# Bio_v4_LCD.net
KiCad netlist of a schematic drawn in EAGLE
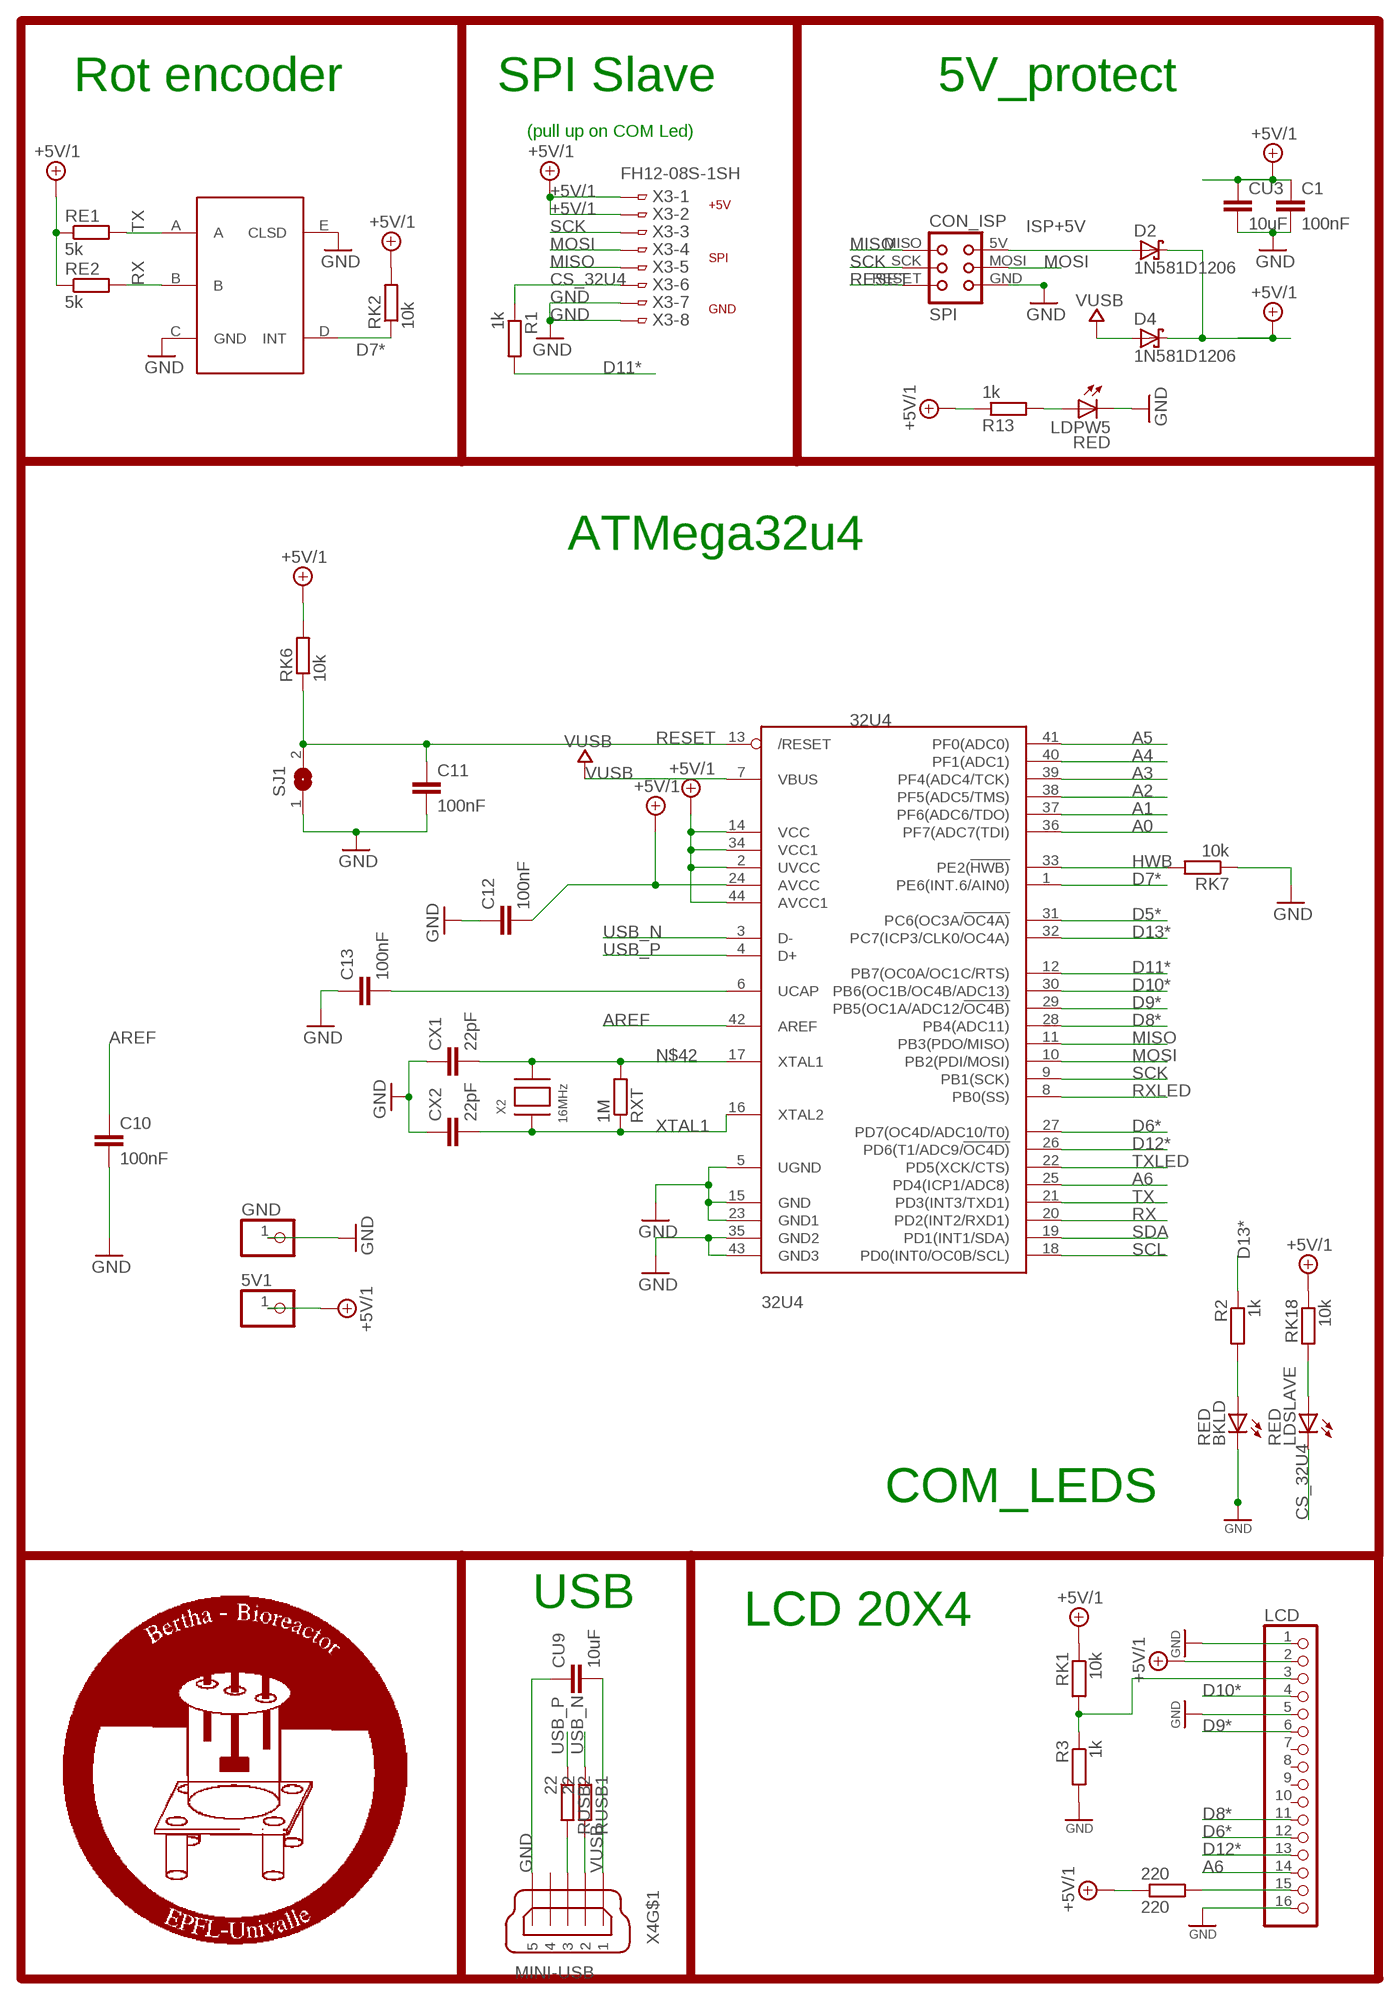
[diagram p0: schematic, sheet 1]

(export (version "E")
  (design (tool "Eeschema 10.0.6"))
  (components
    (comp (ref "5V1")
      (value "PINHD-1X1")
      (footprint "eagle-import:1X01")
      (libsource (lib "eagle-import") (part "PINHD-1X1"))
    )
    (comp (ref "32U4")
      (value "32U4")
      (footprint "eagle-import:TQFP44")
      (libsource (lib "eagle-import") (part "ATMEGA32U4-AU"))
    )
    (comp (ref "220")
      (value "220")
      (footprint "eagle-import:R0805")
      (libsource (lib "eagle-import") (part "R-EU_R0805"))
    )
    (comp (ref "BKLD")
      (value "RED")
      (footprint "eagle-import:CHIP-LED0805")
      (libsource (lib "eagle-import") (part "LEDCHIP-LED0805"))
    )
    (comp (ref "C1")
      (value "100nF")
      (footprint "eagle-import:C1206")
      (libsource (lib "eagle-import") (part "C-EUC1206"))
    )
    (comp (ref "C10")
      (value "100nF")
      (footprint "eagle-import:C1206")
      (libsource (lib "eagle-import") (part "C-EUC1206"))
    )
    (comp (ref "C11")
      (value "100nF")
      (footprint "eagle-import:C1206")
      (libsource (lib "eagle-import") (part "C-EUC1206"))
    )
    (comp (ref "C12")
      (value "100nF")
      (footprint "eagle-import:C1206")
      (libsource (lib "eagle-import") (part "C-EUC1206"))
    )
    (comp (ref "C13")
      (value "100nF")
      (footprint "eagle-import:C1206")
      (libsource (lib "eagle-import") (part "C-EUC1206"))
    )
    (comp (ref "CON_ISP")
      (value "SPI")
      (footprint "eagle-import:TC2030-MCP-NL")
      (libsource (lib "eagle-import") (part "TINYISPT"))
    )
    (comp (ref "CU3")
      (value "10uF")
      (footprint "eagle-import:C1206")
      (libsource (lib "eagle-import") (part "C-EUC1206"))
    )
    (comp (ref "CU9")
      (value "10uF")
      (footprint "eagle-import:C1206")
      (libsource (lib "eagle-import") (part "C-EUC1206"))
    )
    (comp (ref "CX1")
      (value "22pF")
      (footprint "eagle-import:C1206")
      (libsource (lib "eagle-import") (part "C-EUC1206"))
    )
    (comp (ref "CX2")
      (value "22pF")
      (footprint "eagle-import:C1206")
      (libsource (lib "eagle-import") (part "C-EUC1206"))
    )
    (comp (ref "D2")
      (value "1N581D1206")
      (footprint "eagle-import:LED-1206")
      (libsource (lib "eagle-import") (part "1N581D1206"))
    )
    (comp (ref "D4")
      (value "1N581D1206")
      (footprint "eagle-import:LED-1206")
      (libsource (lib "eagle-import") (part "1N581D1206"))
    )
    (comp (ref "GND")
      (value "PINHD-1X1")
      (footprint "eagle-import:1X01")
      (libsource (lib "eagle-import") (part "PINHD-1X1"))
    )
    (comp (ref "LCD")
      (value "LCD-HEADER")
      (footprint "eagle-import:1X16")
      (libsource (lib "eagle-import") (part "LCD-HEADER"))
    )
    (comp (ref "LDPW5")
      (value "RED")
      (footprint "eagle-import:CHIP-LED0805")
      (libsource (lib "eagle-import") (part "LEDCHIP-LED0805"))
    )
    (comp (ref "LDSLAVE")
      (value "RED")
      (footprint "eagle-import:CHIP-LED0805")
      (libsource (lib "eagle-import") (part "LEDCHIP-LED0805"))
    )
    (comp (ref "R1")
      (value "1k")
      (footprint "eagle-import:R0805")
      (libsource (lib "eagle-import") (part "R-EU_R0805"))
    )
    (comp (ref "R2")
      (value "1k")
      (footprint "eagle-import:R0805")
      (libsource (lib "eagle-import") (part "R-EU_R0805"))
    )
    (comp (ref "R3")
      (value "1k")
      (footprint "eagle-import:R0805")
      (libsource (lib "eagle-import") (part "R-EU_R0805"))
    )
    (comp (ref "R13")
      (value "1k")
      (footprint "eagle-import:R0805")
      (libsource (lib "eagle-import") (part "resistor_R-EU_R0805"))
    )
    (comp (ref "RE1")
      (value "5k")
      (footprint "eagle-import:R0805")
      (libsource (lib "eagle-import") (part "R-EU_R0805"))
    )
    (comp (ref "RE2")
      (value "5k")
      (footprint "eagle-import:R0805")
      (libsource (lib "eagle-import") (part "R-EU_R0805"))
    )
    (comp (ref "RK1")
      (value "10k")
      (footprint "eagle-import:R0805")
      (libsource (lib "eagle-import") (part "R-EU_R0805"))
    )
    (comp (ref "RK2")
      (value "10k")
      (footprint "eagle-import:M0805")
      (libsource (lib "eagle-import") (part "resistor_R-EU_M0805"))
    )
    (comp (ref "RK6")
      (value "10k")
      (footprint "eagle-import:M0805")
      (libsource (lib "eagle-import") (part "resistor_R-EU_M0805"))
    )
    (comp (ref "RK7")
      (value "10k")
      (footprint "eagle-import:M0805")
      (libsource (lib "eagle-import") (part "resistor_R-EU_M0805"))
    )
    (comp (ref "RK18")
      (value "10k")
      (footprint "eagle-import:R0805")
      (libsource (lib "eagle-import") (part "R-EU_R0805"))
    )
    (comp (ref "RUSB1")
      (value "22")
      (footprint "eagle-import:M1206")
      (libsource (lib "eagle-import") (part "resistor_R-EU_M1206"))
    )
    (comp (ref "RUSB2")
      (value "22")
      (footprint "eagle-import:M1206")
      (libsource (lib "eagle-import") (part "resistor_R-EU_M1206"))
    )
    (comp (ref "RXT")
      (value "1M")
      (footprint "eagle-import:R0805")
      (libsource (lib "eagle-import") (part "R-EU_R0805"))
    )
    (comp (ref "SJ1") (value "SJ") (footprint "eagle-import:SJ") (libsource (lib "eagle-import") (part "SJ")))
    (comp (ref "U$1")
      (value "EC11E")
      (footprint "eagle-import:EC11E")
      (libsource (lib "eagle-import") (part "EC11E"))
    )
    (comp (ref "X2")
      (value "16MHz")
      (footprint "eagle-import:NX6035")
      (libsource (lib "eagle-import") (part "XTALNX6035"))
    )
    (comp (ref "X3")
      (value "FH12-08S-1SH")
      (footprint "eagle-import:FH12-08S-1SH")
      (libsource (lib "eagle-import") (part "FH12-08S-1SH"))
    )
    (comp (ref "X4")
      (value "MINI-USB")
      (footprint "eagle-import:32005-201")
      (libsource (lib "eagle-import") (part "MINI-USB-SCHIELD-32005-201"))
    )
  )
  (nets
    (net (code "1") (name "+5V{slash}1") (class "Default")
      (node (ref "220") (pin "1") (pinfunction "1_1") (pintype "passive"))
      (node (ref "32U4") (pin "14") (pinfunction "VCC_14") (pintype "bidirectional"))
      (node (ref "32U4") (pin "2") (pinfunction "UVCC_2") (pintype "bidirectional"))
      (node (ref "32U4") (pin "24") (pinfunction "AVCC_24") (pintype "bidirectional"))
      (node (ref "32U4") (pin "34") (pinfunction "VCC1_34") (pintype "bidirectional"))
      (node (ref "32U4") (pin "44") (pinfunction "AVCC1_44") (pintype "bidirectional"))
      (node (ref "5V1") (pin "1") (pinfunction "1_1") (pintype "passive"))
      (node (ref "C1") (pin "1") (pinfunction "1_1") (pintype "passive"))
      (node (ref "C12") (pin "2") (pinfunction "2_2") (pintype "passive"))
      (node (ref "CU3") (pin "1") (pinfunction "1_1") (pintype "passive"))
      (node (ref "D2") (pin "C") (pinfunction "C_C") (pintype "passive"))
      (node (ref "D4") (pin "C") (pinfunction "C_C") (pintype "passive"))
      (node (ref "LCD") (pin "2") (pinfunction "2_2") (pintype "passive"))
      (node (ref "R13") (pin "1") (pinfunction "1_1") (pintype "passive"))
      (node (ref "RE1") (pin "1") (pinfunction "1_1") (pintype "passive"))
      (node (ref "RE2") (pin "1") (pinfunction "1_1") (pintype "passive"))
      (node (ref "RK1") (pin "1") (pinfunction "1_1") (pintype "passive"))
      (node (ref "RK18") (pin "1") (pinfunction "1_1") (pintype "passive"))
      (node (ref "RK2") (pin "2") (pinfunction "2_2") (pintype "passive"))
      (node (ref "RK6") (pin "2") (pinfunction "2_2") (pintype "passive"))
      (node (ref "X3") (pin "1") (pinfunction "1_1") (pintype "passive"))
      (node (ref "X3") (pin "2") (pinfunction "1_2") (pintype "passive"))
    )
    (net (code "2") (name "/A0") (class "Default")
      (node (ref "32U4") (pin "36") (pinfunction "PF7(ADC7(TDI)_36") (pintype "bidirectional"))
    )
    (net (code "3") (name "/A1") (class "Default")
      (node (ref "32U4") (pin "37") (pinfunction "PF6(ADC6/TDO)_37") (pintype "bidirectional"))
    )
    (net (code "4") (name "/A2") (class "Default")
      (node (ref "32U4") (pin "38") (pinfunction "PF5(ADC5/TMS)_38") (pintype "bidirectional"))
    )
    (net (code "5") (name "/A3") (class "Default")
      (node (ref "32U4") (pin "39") (pinfunction "PF4(ADC4/TCK)_39") (pintype "bidirectional"))
    )
    (net (code "6") (name "/A4") (class "Default")
      (node (ref "32U4") (pin "40") (pinfunction "PF1(ADC1)_40") (pintype "bidirectional"))
    )
    (net (code "7") (name "/A5") (class "Default")
      (node (ref "32U4") (pin "41") (pinfunction "PF0(ADC0)_41") (pintype "bidirectional"))
    )
    (net (code "8") (name "/A6") (class "Default")
      (node (ref "32U4") (pin "25") (pinfunction "PD4(ICP1/ADC8)_25") (pintype "bidirectional"))
      (node (ref "LCD") (pin "14") (pinfunction "14_14") (pintype "passive"))
    )
    (net (code "9") (name "/AREF") (class "Default")
      (node (ref "32U4") (pin "42") (pinfunction "AREF_42") (pintype "bidirectional"))
      (node (ref "C10") (pin "1") (pinfunction "1_1") (pintype "passive"))
    )
    (net (code "10") (name "/CS_32U4") (class "Default")
      (node (ref "LDSLAVE") (pin "C") (pinfunction "C_C") (pintype "passive"))
      (node (ref "R1") (pin "1") (pinfunction "1_1") (pintype "passive"))
      (node (ref "X3") (pin "6") (pinfunction "1_6") (pintype "passive"))
    )
    (net (code "11") (name "/D5*") (class "Default")
      (node (ref "32U4") (pin "31") (pinfunction "PC6(OC3A/~{OC4A})_31") (pintype "bidirectional"))
    )
    (net (code "12") (name "/D6*") (class "Default")
      (node (ref "32U4") (pin "27") (pinfunction "PD7(OC4D/ADC10/T0)_27") (pintype "bidirectional"))
      (node (ref "LCD") (pin "12") (pinfunction "12_12") (pintype "passive"))
    )
    (net (code "13") (name "/D7*") (class "Default")
      (node (ref "32U4") (pin "1") (pinfunction "PE6(INT.6/AIN0)_1") (pintype "bidirectional"))
      (node (ref "RK2") (pin "1") (pinfunction "1_1") (pintype "passive"))
      (node (ref "U$1") (pin "D") (pinfunction "INT_D") (pintype "bidirectional"))
    )
    (net (code "14") (name "/D8*") (class "Default")
      (node (ref "32U4") (pin "28") (pinfunction "PB4(ADC11)_28") (pintype "bidirectional"))
      (node (ref "LCD") (pin "11") (pinfunction "11_11") (pintype "passive"))
    )
    (net (code "15") (name "/D9*") (class "Default")
      (node (ref "32U4") (pin "29") (pinfunction "PB5(OC1A/ADC12/~{OC4B})_29") (pintype "bidirectional"))
      (node (ref "LCD") (pin "6") (pinfunction "6_6") (pintype "passive"))
    )
    (net (code "16") (name "/D10*") (class "Default")
      (node (ref "32U4") (pin "30") (pinfunction "PB6(OC1B/OC4B/ADC13)_30") (pintype "bidirectional"))
      (node (ref "LCD") (pin "4") (pinfunction "4_4") (pintype "passive"))
    )
    (net (code "17") (name "/D11*") (class "Default")
      (node (ref "32U4") (pin "12") (pinfunction "PB7(OC0A/OC1C/RTS)_12") (pintype "bidirectional"))
      (node (ref "R1") (pin "2") (pinfunction "2_2") (pintype "passive"))
    )
    (net (code "18") (name "/D12*") (class "Default")
      (node (ref "32U4") (pin "26") (pinfunction "PD6(T1/ADC9/~{OC4D})_26") (pintype "bidirectional"))
      (node (ref "LCD") (pin "13") (pinfunction "13_13") (pintype "passive"))
    )
    (net (code "19") (name "/D13*") (class "Default")
      (node (ref "32U4") (pin "32") (pinfunction "PC7(ICP3/CLK0/OC4A)_32") (pintype "bidirectional"))
      (node (ref "R2") (pin "1") (pinfunction "1_1") (pintype "passive"))
    )
    (net (code "20") (name "/HWB") (class "Default")
      (node (ref "32U4") (pin "33") (pinfunction "PE2(~{HWB})_33") (pintype "bidirectional"))
      (node (ref "RK7") (pin "2") (pinfunction "2_2") (pintype "passive"))
    )
    (net (code "21") (name "/ISP+5V") (class "Default")
      (node (ref "CON_ISP") (pin "5V") (pinfunction "VCC_5V") (pintype "passive"))
      (node (ref "D2") (pin "A") (pinfunction "A_A") (pintype "passive"))
    )
    (net (code "22") (name "/MISO") (class "Default")
      (node (ref "32U4") (pin "11") (pinfunction "PB3(PDO/MISO)_11") (pintype "bidirectional"))
      (node (ref "CON_ISP") (pin "MISO") (pinfunction "MISO_MISO") (pintype "passive"))
      (node (ref "X3") (pin "5") (pinfunction "1_5") (pintype "passive"))
    )
    (net (code "23") (name "/MOSI") (class "Default")
      (node (ref "32U4") (pin "10") (pinfunction "PB2(PDI/MOSI)_10") (pintype "bidirectional"))
      (node (ref "CON_ISP") (pin "MOSI") (pinfunction "MOSI_MOSI") (pintype "passive"))
      (node (ref "X3") (pin "4") (pinfunction "1_4") (pintype "passive"))
    )
    (net (code "24") (name "/N$42") (class "Default")
      (node (ref "32U4") (pin "17") (pinfunction "XTAL1_17") (pintype "bidirectional"))
      (node (ref "CX1") (pin "2") (pinfunction "2_2") (pintype "passive"))
      (node (ref "RXT") (pin "2") (pinfunction "2_2") (pintype "passive"))
      (node (ref "X2") (pin "P$2") (pinfunction "P$2_P$2") (pintype "bidirectional"))
    )
    (net (code "25") (name "/RESET") (class "Default")
      (node (ref "32U4") (pin "13") (pinfunction "/RESET_13") (pintype "bidirectional"))
      (node (ref "C11") (pin "1") (pinfunction "1_1") (pintype "passive"))
      (node (ref "CON_ISP") (pin "RESET") (pinfunction "RESET_RESET") (pintype "passive"))
      (node (ref "RK6") (pin "1") (pinfunction "1_1") (pintype "passive"))
      (node (ref "SJ1") (pin "2") (pinfunction "2_2") (pintype "passive"))
    )
    (net (code "26") (name "/RX") (class "Default")
      (node (ref "32U4") (pin "20") (pinfunction "PD2(INT2/RXD1)_20") (pintype "bidirectional"))
      (node (ref "RE2") (pin "2") (pinfunction "2_2") (pintype "passive"))
      (node (ref "U$1") (pin "B") (pinfunction "B_B") (pintype "bidirectional"))
    )
    (net (code "27") (name "/RXLED") (class "Default")
      (node (ref "32U4") (pin "8") (pinfunction "PB0(SS)_8") (pintype "bidirectional"))
    )
    (net (code "28") (name "/SCK") (class "Default")
      (node (ref "32U4") (pin "9") (pinfunction "PB1(SCK)_9") (pintype "bidirectional"))
      (node (ref "CON_ISP") (pin "SCK") (pinfunction "SCK_SCK") (pintype "passive"))
      (node (ref "X3") (pin "3") (pinfunction "1_3") (pintype "passive"))
    )
    (net (code "29") (name "/SCL") (class "Default")
      (node (ref "32U4") (pin "18") (pinfunction "PD0(INT0/OC0B/SCL)_18") (pintype "bidirectional"))
    )
    (net (code "30") (name "/SDA") (class "Default")
      (node (ref "32U4") (pin "19") (pinfunction "PD1(INT1/SDA)_19") (pintype "bidirectional"))
    )
    (net (code "31") (name "/TX") (class "Default")
      (node (ref "32U4") (pin "21") (pinfunction "PD3(INT3/TXD1)_21") (pintype "bidirectional"))
      (node (ref "RE1") (pin "2") (pinfunction "2_2") (pintype "passive"))
      (node (ref "U$1") (pin "A") (pinfunction "A_A") (pintype "bidirectional"))
    )
    (net (code "32") (name "/TXLED") (class "Default")
      (node (ref "32U4") (pin "22") (pinfunction "PD5(XCK/CTS)_22") (pintype "bidirectional"))
    )
    (net (code "33") (name "/USB_N") (class "Default")
      (node (ref "32U4") (pin "3") (pinfunction "D-_3") (pintype "bidirectional"))
      (node (ref "RUSB1") (pin "1") (pinfunction "1_1") (pintype "passive"))
    )
    (net (code "34") (name "/USB_P") (class "Default")
      (node (ref "32U4") (pin "4") (pinfunction "D+_4") (pintype "bidirectional"))
      (node (ref "RUSB2") (pin "1") (pinfunction "1_1") (pintype "passive"))
    )
    (net (code "35") (name "/XTAL1") (class "Default")
      (node (ref "32U4") (pin "16") (pinfunction "XTAL2_16") (pintype "bidirectional"))
      (node (ref "CX2") (pin "2") (pinfunction "2_2") (pintype "passive"))
      (node (ref "RXT") (pin "1") (pinfunction "1_1") (pintype "passive"))
      (node (ref "X2") (pin "P$1") (pinfunction "P$1_P$1") (pintype "bidirectional"))
    )
    (net (code "36") (name "GND") (class "Default")
      (node (ref "32U4") (pin "15") (pinfunction "GND_15") (pintype "bidirectional"))
      (node (ref "32U4") (pin "23") (pinfunction "GND1_23") (pintype "bidirectional"))
      (node (ref "32U4") (pin "35") (pinfunction "GND2_35") (pintype "bidirectional"))
      (node (ref "32U4") (pin "43") (pinfunction "GND3_43") (pintype "bidirectional"))
      (node (ref "32U4") (pin "5") (pinfunction "UGND_5") (pintype "bidirectional"))
      (node (ref "BKLD") (pin "C") (pinfunction "C_C") (pintype "passive"))
      (node (ref "C1") (pin "2") (pinfunction "2_2") (pintype "passive"))
      (node (ref "C10") (pin "2") (pinfunction "2_2") (pintype "passive"))
      (node (ref "C11") (pin "2") (pinfunction "2_2") (pintype "passive"))
      (node (ref "C12") (pin "1") (pinfunction "1_1") (pintype "passive"))
      (node (ref "C13") (pin "1") (pinfunction "1_1") (pintype "passive"))
      (node (ref "CON_ISP") (pin "GND") (pinfunction "GND_GND") (pintype "passive"))
      (node (ref "CU3") (pin "2") (pinfunction "2_2") (pintype "passive"))
      (node (ref "CU9") (pin "1") (pinfunction "1_1") (pintype "passive"))
      (node (ref "CX1") (pin "1") (pinfunction "1_1") (pintype "passive"))
      (node (ref "CX2") (pin "1") (pinfunction "1_1") (pintype "passive"))
      (node (ref "GND") (pin "1") (pinfunction "1_1") (pintype "passive"))
      (node (ref "LCD") (pin "1") (pinfunction "1_1") (pintype "passive"))
      (node (ref "LCD") (pin "16") (pinfunction "16_16") (pintype "passive"))
      (node (ref "LCD") (pin "5") (pinfunction "5_5") (pintype "passive"))
      (node (ref "LDPW5") (pin "C") (pinfunction "C_C") (pintype "passive"))
      (node (ref "R3") (pin "2") (pinfunction "2_2") (pintype "passive"))
      (node (ref "RK7") (pin "1") (pinfunction "1_1") (pintype "passive"))
      (node (ref "SJ1") (pin "1") (pinfunction "1_1") (pintype "passive"))
      (node (ref "U$1") (pin "C") (pinfunction "GND_C") (pintype "bidirectional"))
      (node (ref "U$1") (pin "E") (pinfunction "CLSD_E") (pintype "bidirectional"))
      (node (ref "X3") (pin "7") (pinfunction "1_7") (pintype "passive"))
      (node (ref "X3") (pin "8") (pinfunction "1_8") (pintype "passive"))
      (node (ref "X4") (pin "5") (pinfunction "5_5") (pintype "passive"))
    )
    (net (code "37") (name "Net-(32U4-UCAP)") (class "Default")
      (node (ref "32U4") (pin "6") (pinfunction "UCAP_6") (pintype "bidirectional"))
      (node (ref "C13") (pin "2") (pinfunction "2_2") (pintype "passive"))
    )
    (net (code "38") (name "Net-(220-Pad2)") (class "Default")
      (node (ref "220") (pin "2") (pinfunction "2_2") (pintype "passive"))
      (node (ref "LCD") (pin "15") (pinfunction "15_15") (pintype "passive"))
    )
    (net (code "39") (name "Net-(BKLD-PadA)") (class "Default")
      (node (ref "BKLD") (pin "A") (pinfunction "A_A") (pintype "passive"))
      (node (ref "R2") (pin "2") (pinfunction "2_2") (pintype "passive"))
    )
    (net (code "40") (name "Net-(LCD-Pad3)") (class "Default")
      (node (ref "LCD") (pin "3") (pinfunction "3_3") (pintype "passive"))
      (node (ref "R3") (pin "1") (pinfunction "1_1") (pintype "passive"))
      (node (ref "RK1") (pin "2") (pinfunction "2_2") (pintype "passive"))
    )
    (net (code "41") (name "Net-(LDPW5-PadA)") (class "Default")
      (node (ref "LDPW5") (pin "A") (pinfunction "A_A") (pintype "passive"))
      (node (ref "R13") (pin "2") (pinfunction "2_2") (pintype "passive"))
    )
    (net (code "42") (name "Net-(LDSLAVE-PadA)") (class "Default")
      (node (ref "LDSLAVE") (pin "A") (pinfunction "A_A") (pintype "passive"))
      (node (ref "RK18") (pin "2") (pinfunction "2_2") (pintype "passive"))
    )
    (net (code "43") (name "Net-(RUSB1-Pad2)") (class "Default")
      (node (ref "RUSB1") (pin "2") (pinfunction "2_2") (pintype "passive"))
      (node (ref "X4") (pin "2") (pinfunction "2_2") (pintype "passive"))
    )
    (net (code "44") (name "Net-(RUSB2-Pad2)") (class "Default")
      (node (ref "RUSB2") (pin "2") (pinfunction "2_2") (pintype "passive"))
      (node (ref "X4") (pin "3") (pinfunction "3_3") (pintype "passive"))
    )
    (net (code "45") (name "VUSB") (class "Default")
      (node (ref "32U4") (pin "7") (pinfunction "VBUS_7") (pintype "bidirectional"))
      (node (ref "CU9") (pin "2") (pinfunction "2_2") (pintype "passive"))
      (node (ref "D4") (pin "A") (pinfunction "A_A") (pintype "passive"))
      (node (ref "X4") (pin "1") (pinfunction "1_1") (pintype "passive"))
    )
    (net (code "46") (name "unconnected-(LCD-Pad7)") (class "Default")
      (node (ref "LCD") (pin "7") (pinfunction "7_7") (pintype "passive"))
    )
    (net (code "47") (name "unconnected-(LCD-Pad8)") (class "Default")
      (node (ref "LCD") (pin "8") (pinfunction "8_8") (pintype "passive"))
    )
    (net (code "48") (name "unconnected-(LCD-Pad9)") (class "Default")
      (node (ref "LCD") (pin "9") (pinfunction "9_9") (pintype "passive"))
    )
    (net (code "49") (name "unconnected-(LCD-Pad10)") (class "Default")
      (node (ref "LCD") (pin "10") (pinfunction "10_10") (pintype "passive"))
    )
    (net (code "50") (name "unconnected-(X4-Pad4)") (class "Default")
      (node (ref "X4") (pin "4") (pinfunction "4_4") (pintype "passive"))
    )
  )
)
